# combo_-_no_usb_-_pth_-_gp2s700.net
KiCad netlist of a schematic drawn in EAGLE
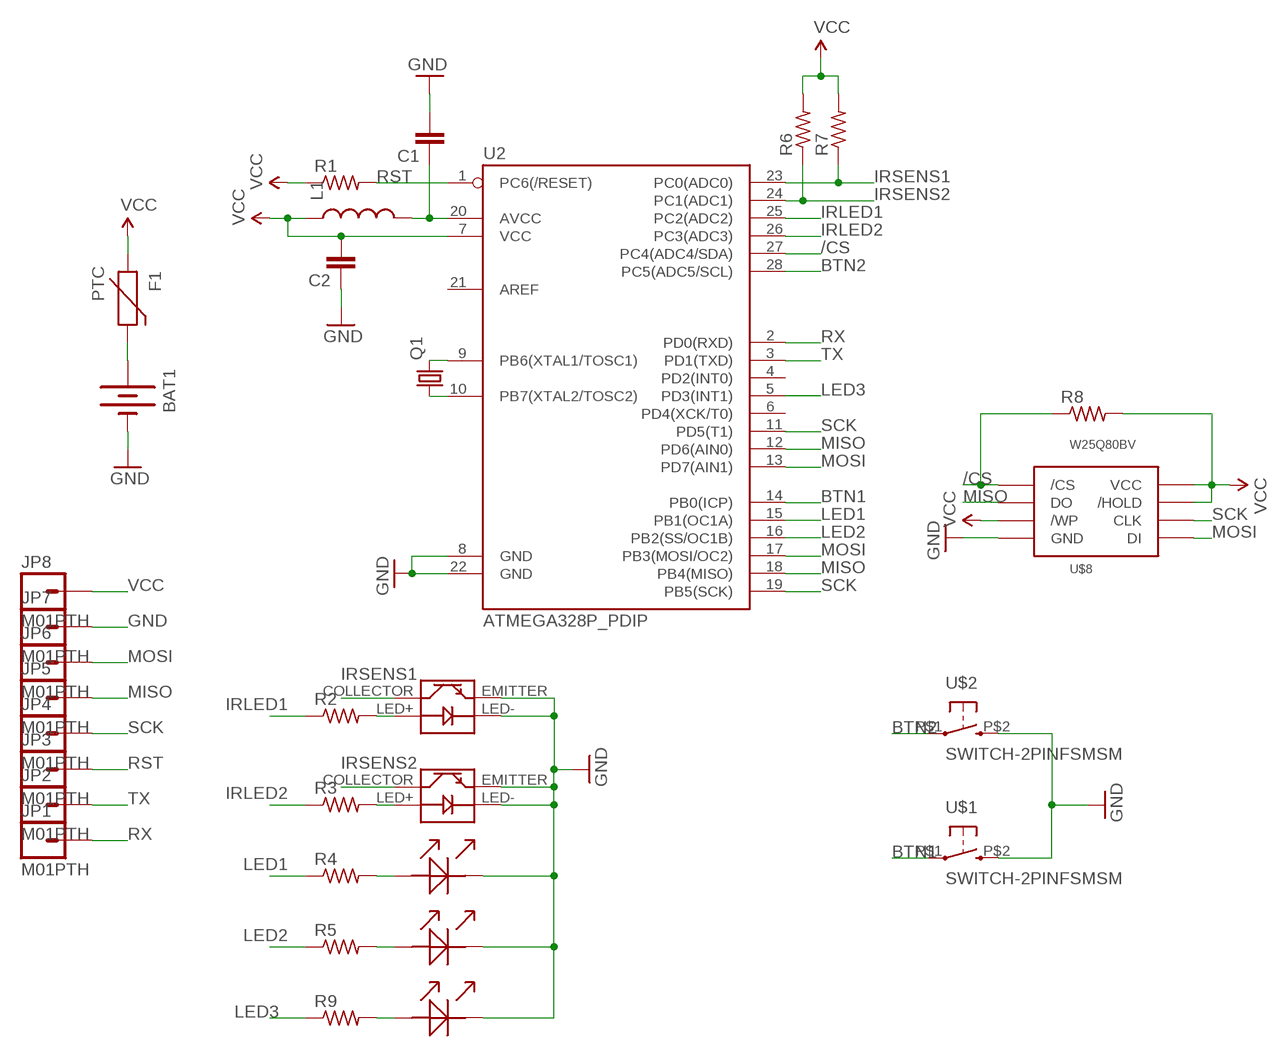
[diagram p0: schematic, sheet 1]

(export (version "E")
  (design (tool "Eeschema 10.0.6"))
  (components
    (comp (ref "BAT1")
      (value "BATTERYBA2032SM")
      (footprint "eagle-import:BA2032SM")
      (libsource (lib "eagle-import") (part "BATTERYBA2032SM"))
    )
    (comp (ref "C1")
      (value "CAP0805")
      (footprint "eagle-import:0805")
      (libsource (lib "eagle-import") (part "CAP0805"))
    )
    (comp (ref "C2")
      (value "CAP0805")
      (footprint "eagle-import:0805")
      (libsource (lib "eagle-import") (part "CAP0805"))
    )
    (comp (ref "F1")
      (value "PTC")
      (footprint "eagle-import:R0805")
      (libsource (lib "eagle-import") (part "PTC"))
    )
    (comp (ref "JP1")
      (value "M01PTH")
      (footprint "eagle-import:1X01")
      (libsource (lib "eagle-import") (part "M01PTH"))
    )
    (comp (ref "JP2")
      (value "M01PTH")
      (footprint "eagle-import:1X01")
      (libsource (lib "eagle-import") (part "M01PTH"))
    )
    (comp (ref "JP3")
      (value "M01PTH")
      (footprint "eagle-import:1X01")
      (libsource (lib "eagle-import") (part "M01PTH"))
    )
    (comp (ref "JP4")
      (value "M01PTH")
      (footprint "eagle-import:1X01")
      (libsource (lib "eagle-import") (part "M01PTH"))
    )
    (comp (ref "JP5")
      (value "M01PTH")
      (footprint "eagle-import:1X01")
      (libsource (lib "eagle-import") (part "M01PTH"))
    )
    (comp (ref "JP6")
      (value "M01PTH")
      (footprint "eagle-import:1X01")
      (libsource (lib "eagle-import") (part "M01PTH"))
    )
    (comp (ref "JP7")
      (value "M01PTH")
      (footprint "eagle-import:1X01")
      (libsource (lib "eagle-import") (part "M01PTH"))
    )
    (comp (ref "JP8")
      (value "M01PTH")
      (footprint "eagle-import:1X01")
      (libsource (lib "eagle-import") (part "M01PTH"))
    )
    (comp (ref "L1")
      (value "INDUCTOR0805")
      (footprint "eagle-import:0805")
      (libsource (lib "eagle-import") (part "INDUCTOR0805"))
    )
    (comp (ref "Q1")
      (value "CRYSTALTC26V")
      (footprint "eagle-import:TC26V")
      (libsource (lib "eagle-import") (part "CRYSTALTC26V"))
    )
    (comp (ref "R1")
      (value "R-US_M0805")
      (footprint "eagle-import:M0805")
      (libsource (lib "eagle-import") (part "R-US_M0805"))
    )
    (comp (ref "R2")
      (value "R-US_M0805")
      (footprint "eagle-import:M0805")
      (libsource (lib "eagle-import") (part "R-US_M0805"))
    )
    (comp (ref "R3")
      (value "R-US_M0805")
      (footprint "eagle-import:M0805")
      (libsource (lib "eagle-import") (part "R-US_M0805"))
    )
    (comp (ref "R4")
      (value "R-US_M0805")
      (footprint "eagle-import:M0805")
      (libsource (lib "eagle-import") (part "R-US_M0805"))
    )
    (comp (ref "R5")
      (value "R-US_M0805")
      (footprint "eagle-import:M0805")
      (libsource (lib "eagle-import") (part "R-US_M0805"))
    )
    (comp (ref "R6")
      (value "R-US_M0805")
      (footprint "eagle-import:M0805")
      (libsource (lib "eagle-import") (part "R-US_M0805"))
    )
    (comp (ref "R7")
      (value "R-US_M0805")
      (footprint "eagle-import:M0805")
      (libsource (lib "eagle-import") (part "R-US_M0805"))
    )
    (comp (ref "R8")
      (value "R-US_M0805")
      (footprint "eagle-import:M0805")
      (libsource (lib "eagle-import") (part "R-US_M0805"))
    )
    (comp (ref "R9")
      (value "R-US_M0805")
      (footprint "eagle-import:M0805")
      (libsource (lib "eagle-import") (part "R-US_M0805"))
    )
    (comp (ref "U$1")
      (value "SWITCH-2PINFSMSM")
      (footprint "eagle-import:FSMSM-BUTTON")
      (libsource (lib "eagle-import") (part "SWITCH-2PINFSMSM"))
    )
    (comp (ref "U$2")
      (value "SWITCH-2PINFSMSM")
      (footprint "eagle-import:FSMSM-BUTTON")
      (libsource (lib "eagle-import") (part "SWITCH-2PINFSMSM"))
    )
    (comp (ref "U$3")
      (value "IR_SENSORGP2S700HCP")
      (footprint "eagle-import:GP2S700HCP")
      (libsource (lib "eagle-import") (part "IR_SENSORGP2S700HCP"))
    )
    (comp (ref "U$4")
      (value "IR_SENSORGP2S700HCP")
      (footprint "eagle-import:GP2S700HCP")
      (libsource (lib "eagle-import") (part "IR_SENSORGP2S700HCP"))
    )
    (comp (ref "U$5")
      (value "LED0603")
      (footprint "eagle-import:0603")
      (libsource (lib "eagle-import") (part "LED0603"))
    )
    (comp (ref "U$6")
      (value "LED0603")
      (footprint "eagle-import:0603")
      (libsource (lib "eagle-import") (part "LED0603"))
    )
    (comp (ref "U$7")
      (value "LED0603")
      (footprint "eagle-import:0603")
      (libsource (lib "eagle-import") (part "LED0603"))
    )
    (comp (ref "U$8")
      (value "W25Q80BVSOIC-08")
      (footprint "eagle-import:W25Q80BV-SOIC-208MIL")
      (libsource (lib "eagle-import") (part "W25Q80BVSOIC-08"))
    )
    (comp (ref "U2")
      (value "ATMEGA328P_PDIP")
      (footprint "eagle-import:DIL28-3")
      (libsource (lib "eagle-import") (part "ATMEGA328P_PDIP"))
    )
  )
  (nets
    (net (code "1") (name "/BTN1") (class "Default")
      (node (ref "U$1") (pin "P$1") (pinfunction "1_P$1") (pintype "passive"))
      (node (ref "U2") (pin "14") (pinfunction "PB0(ICP)_14") (pintype "bidirectional"))
    )
    (net (code "2") (name "/BTN2") (class "Default")
      (node (ref "U$2") (pin "P$1") (pinfunction "1_P$1") (pintype "passive"))
      (node (ref "U2") (pin "28") (pinfunction "PC5(ADC5/SCL)_28") (pintype "bidirectional"))
    )
    (net (code "3") (name "/IRLED1") (class "Default")
      (node (ref "R2") (pin "1") (pinfunction "1_1") (pintype "passive"))
      (node (ref "U2") (pin "25") (pinfunction "PC2(ADC2)_25") (pintype "bidirectional"))
    )
    (net (code "4") (name "/IRLED2") (class "Default")
      (node (ref "R3") (pin "1") (pinfunction "1_1") (pintype "passive"))
      (node (ref "U2") (pin "26") (pinfunction "PC3(ADC3)_26") (pintype "bidirectional"))
    )
    (net (code "5") (name "/IRSENS1") (class "Default")
      (node (ref "R7") (pin "1") (pinfunction "1_1") (pintype "passive"))
      (node (ref "U$3") (pin "COLLECTOR") (pinfunction "COLLECTOR_COLLECTOR") (pintype "input"))
      (node (ref "U2") (pin "23") (pinfunction "PC0(ADC0)_23") (pintype "bidirectional"))
    )
    (net (code "6") (name "/IRSENS2") (class "Default")
      (node (ref "R6") (pin "1") (pinfunction "1_1") (pintype "passive"))
      (node (ref "U$4") (pin "COLLECTOR") (pinfunction "COLLECTOR_COLLECTOR") (pintype "input"))
      (node (ref "U2") (pin "24") (pinfunction "PC1(ADC1)_24") (pintype "bidirectional"))
    )
    (net (code "7") (name "/LED1") (class "Default")
      (node (ref "R4") (pin "1") (pinfunction "1_1") (pintype "passive"))
      (node (ref "U2") (pin "15") (pinfunction "PB1(OC1A)_15") (pintype "bidirectional"))
    )
    (net (code "8") (name "/LED2") (class "Default")
      (node (ref "R5") (pin "1") (pinfunction "1_1") (pintype "passive"))
      (node (ref "U2") (pin "16") (pinfunction "PB2(SS/OC1B)_16") (pintype "bidirectional"))
    )
    (net (code "9") (name "/LED3") (class "Default")
      (node (ref "R9") (pin "1") (pinfunction "1_1") (pintype "passive"))
      (node (ref "U2") (pin "5") (pinfunction "PD3(INT1)_5") (pintype "bidirectional"))
    )
    (net (code "10") (name "/MISO") (class "Default")
      (node (ref "JP5") (pin "1") (pinfunction "1_1") (pintype "passive"))
      (node (ref "U$8") (pin "DO") (pinfunction "DO_DO") (pintype "bidirectional"))
      (node (ref "U2") (pin "12") (pinfunction "PD6(AIN0)_12") (pintype "bidirectional"))
      (node (ref "U2") (pin "18") (pinfunction "PB4(MISO)_18") (pintype "bidirectional"))
    )
    (net (code "11") (name "/MOSI") (class "Default")
      (node (ref "JP6") (pin "1") (pinfunction "1_1") (pintype "passive"))
      (node (ref "U$8") (pin "DI") (pinfunction "DI_DI") (pintype "bidirectional"))
      (node (ref "U2") (pin "13") (pinfunction "PD7(AIN1)_13") (pintype "bidirectional"))
      (node (ref "U2") (pin "17") (pinfunction "PB3(MOSI/OC2)_17") (pintype "bidirectional"))
    )
    (net (code "12") (name "/RST") (class "Default")
      (node (ref "JP3") (pin "1") (pinfunction "1_1") (pintype "passive"))
      (node (ref "R1") (pin "2") (pinfunction "2_2") (pintype "passive"))
      (node (ref "U2") (pin "1") (pinfunction "PC6(/RESET)_1") (pintype "bidirectional"))
    )
    (net (code "13") (name "/RX") (class "Default")
      (node (ref "JP1") (pin "1") (pinfunction "1_1") (pintype "passive"))
      (node (ref "U2") (pin "2") (pinfunction "PD0(RXD)_2") (pintype "bidirectional"))
    )
    (net (code "14") (name "/SCK") (class "Default")
      (node (ref "JP4") (pin "1") (pinfunction "1_1") (pintype "passive"))
      (node (ref "U$8") (pin "CLK") (pinfunction "CLK_CLK") (pintype "input"))
      (node (ref "U2") (pin "11") (pinfunction "PD5(T1)_11") (pintype "bidirectional"))
      (node (ref "U2") (pin "19") (pinfunction "PB5(SCK)_19") (pintype "bidirectional"))
    )
    (net (code "15") (name "/TX") (class "Default")
      (node (ref "JP2") (pin "1") (pinfunction "1_1") (pintype "passive"))
      (node (ref "U2") (pin "3") (pinfunction "PD1(TXD)_3") (pintype "bidirectional"))
    )
    (net (code "16") (name "/{slash}CS") (class "Default")
      (node (ref "R8") (pin "1") (pinfunction "1_1") (pintype "passive"))
      (node (ref "U$8") (pin "/CS") (pinfunction "/CS_/CS") (pintype "input"))
      (node (ref "U2") (pin "27") (pinfunction "PC4(ADC4/SDA)_27") (pintype "bidirectional"))
    )
    (net (code "17") (name "GND") (class "Default")
      (node (ref "BAT1") (pin "-") (pinfunction "-_-") (pintype "power_in"))
      (node (ref "C1") (pin "2") (pinfunction "2_2") (pintype "passive"))
      (node (ref "C2") (pin "1") (pinfunction "1_1") (pintype "passive"))
      (node (ref "JP7") (pin "1") (pinfunction "1_1") (pintype "passive"))
      (node (ref "U$1") (pin "P$2") (pinfunction "3_P$2") (pintype "passive"))
      (node (ref "U$2") (pin "P$2") (pinfunction "3_P$2") (pintype "passive"))
      (node (ref "U$3") (pin "EMITTER") (pinfunction "EMITTER_EMITTER") (pintype "input"))
      (node (ref "U$3") (pin "LED-") (pinfunction "LED-_LED-") (pintype "input"))
      (node (ref "U$4") (pin "EMITTER") (pinfunction "EMITTER_EMITTER") (pintype "input"))
      (node (ref "U$4") (pin "LED-") (pinfunction "LED-_LED-") (pintype "input"))
      (node (ref "U$5") (pin "2") (pinfunction "-_2") (pintype "bidirectional"))
      (node (ref "U$6") (pin "2") (pinfunction "-_2") (pintype "bidirectional"))
      (node (ref "U$7") (pin "2") (pinfunction "-_2") (pintype "bidirectional"))
      (node (ref "U$8") (pin "GND") (pinfunction "GND_GND") (pintype "power_in"))
      (node (ref "U2") (pin "22") (pinfunction "GND_22") (pintype "bidirectional"))
      (node (ref "U2") (pin "8") (pinfunction "GND_8") (pintype "bidirectional"))
    )
    (net (code "18") (name "Net-(BAT1-Pad+)") (class "Default")
      (node (ref "BAT1") (pin "+") (pinfunction "+_+") (pintype "power_in"))
      (node (ref "F1") (pin "2") (pinfunction "2_2") (pintype "bidirectional"))
    )
    (net (code "19") (name "Net-(R2-Pad2)") (class "Default")
      (node (ref "R2") (pin "2") (pinfunction "2_2") (pintype "passive"))
      (node (ref "U$3") (pin "LED+") (pinfunction "LED+_LED+") (pintype "input"))
    )
    (net (code "20") (name "Net-(R3-Pad2)") (class "Default")
      (node (ref "R3") (pin "2") (pinfunction "2_2") (pintype "passive"))
      (node (ref "U$4") (pin "LED+") (pinfunction "LED+_LED+") (pintype "input"))
    )
    (net (code "21") (name "Net-(U$5-+)") (class "Default")
      (node (ref "R4") (pin "2") (pinfunction "2_2") (pintype "passive"))
      (node (ref "U$5") (pin "1") (pinfunction "+_1") (pintype "bidirectional"))
    )
    (net (code "22") (name "Net-(U$6-+)") (class "Default")
      (node (ref "R5") (pin "2") (pinfunction "2_2") (pintype "passive"))
      (node (ref "U$6") (pin "1") (pinfunction "+_1") (pintype "bidirectional"))
    )
    (net (code "23") (name "Net-(U$7-+)") (class "Default")
      (node (ref "R9") (pin "2") (pinfunction "2_2") (pintype "passive"))
      (node (ref "U$7") (pin "1") (pinfunction "+_1") (pintype "bidirectional"))
    )
    (net (code "24") (name "Net-(U2-AVCC)") (class "Default")
      (node (ref "C1") (pin "1") (pinfunction "1_1") (pintype "passive"))
      (node (ref "L1") (pin "2") (pinfunction "2_2") (pintype "passive"))
      (node (ref "U2") (pin "20") (pinfunction "AVCC_20") (pintype "bidirectional"))
    )
    (net (code "25") (name "Net-(U2-PB6(XTAL1{slash}TOSC1))") (class "Default")
      (node (ref "Q1") (pin "2") (pinfunction "2_2") (pintype "passive"))
      (node (ref "U2") (pin "9") (pinfunction "PB6(XTAL1/TOSC1)_9") (pintype "bidirectional"))
    )
    (net (code "26") (name "Net-(U2-PB7(XTAL2{slash}TOSC2))") (class "Default")
      (node (ref "Q1") (pin "1") (pinfunction "1_1") (pintype "passive"))
      (node (ref "U2") (pin "10") (pinfunction "PB7(XTAL2/TOSC2)_10") (pintype "bidirectional"))
    )
    (net (code "27") (name "VCC") (class "Default")
      (node (ref "C2") (pin "2") (pinfunction "2_2") (pintype "passive"))
      (node (ref "F1") (pin "1") (pinfunction "1_1") (pintype "bidirectional"))
      (node (ref "JP8") (pin "1") (pinfunction "1_1") (pintype "passive"))
      (node (ref "L1") (pin "1") (pinfunction "1_1") (pintype "passive"))
      (node (ref "R1") (pin "1") (pinfunction "1_1") (pintype "passive"))
      (node (ref "R6") (pin "2") (pinfunction "2_2") (pintype "passive"))
      (node (ref "R7") (pin "2") (pinfunction "2_2") (pintype "passive"))
      (node (ref "R8") (pin "2") (pinfunction "2_2") (pintype "passive"))
      (node (ref "U$8") (pin "/HOLD") (pinfunction "/HOLD_/HOLD") (pintype "bidirectional"))
      (node (ref "U$8") (pin "/WP") (pinfunction "/WP_/WP") (pintype "bidirectional"))
      (node (ref "U$8") (pin "VCC") (pinfunction "VCC_VCC") (pintype "power_in"))
      (node (ref "U2") (pin "7") (pinfunction "VCC_7") (pintype "bidirectional"))
    )
    (net (code "28") (name "unconnected-(U2-AREF-Pad21)") (class "Default")
      (node (ref "U2") (pin "21") (pinfunction "AREF_21") (pintype "bidirectional"))
    )
    (net (code "29") (name "unconnected-(U2-PD2(INT0)-Pad4)") (class "Default")
      (node (ref "U2") (pin "4") (pinfunction "PD2(INT0)_4") (pintype "bidirectional"))
    )
    (net (code "30") (name "unconnected-(U2-PD4(XCK{slash}T0)-Pad6)") (class "Default")
      (node (ref "U2") (pin "6") (pinfunction "PD4(XCK/T0)_6") (pintype "bidirectional"))
    )
  )
)
